# Peripherals.net
KiCad netlist of a schematic drawn in Altium Designer
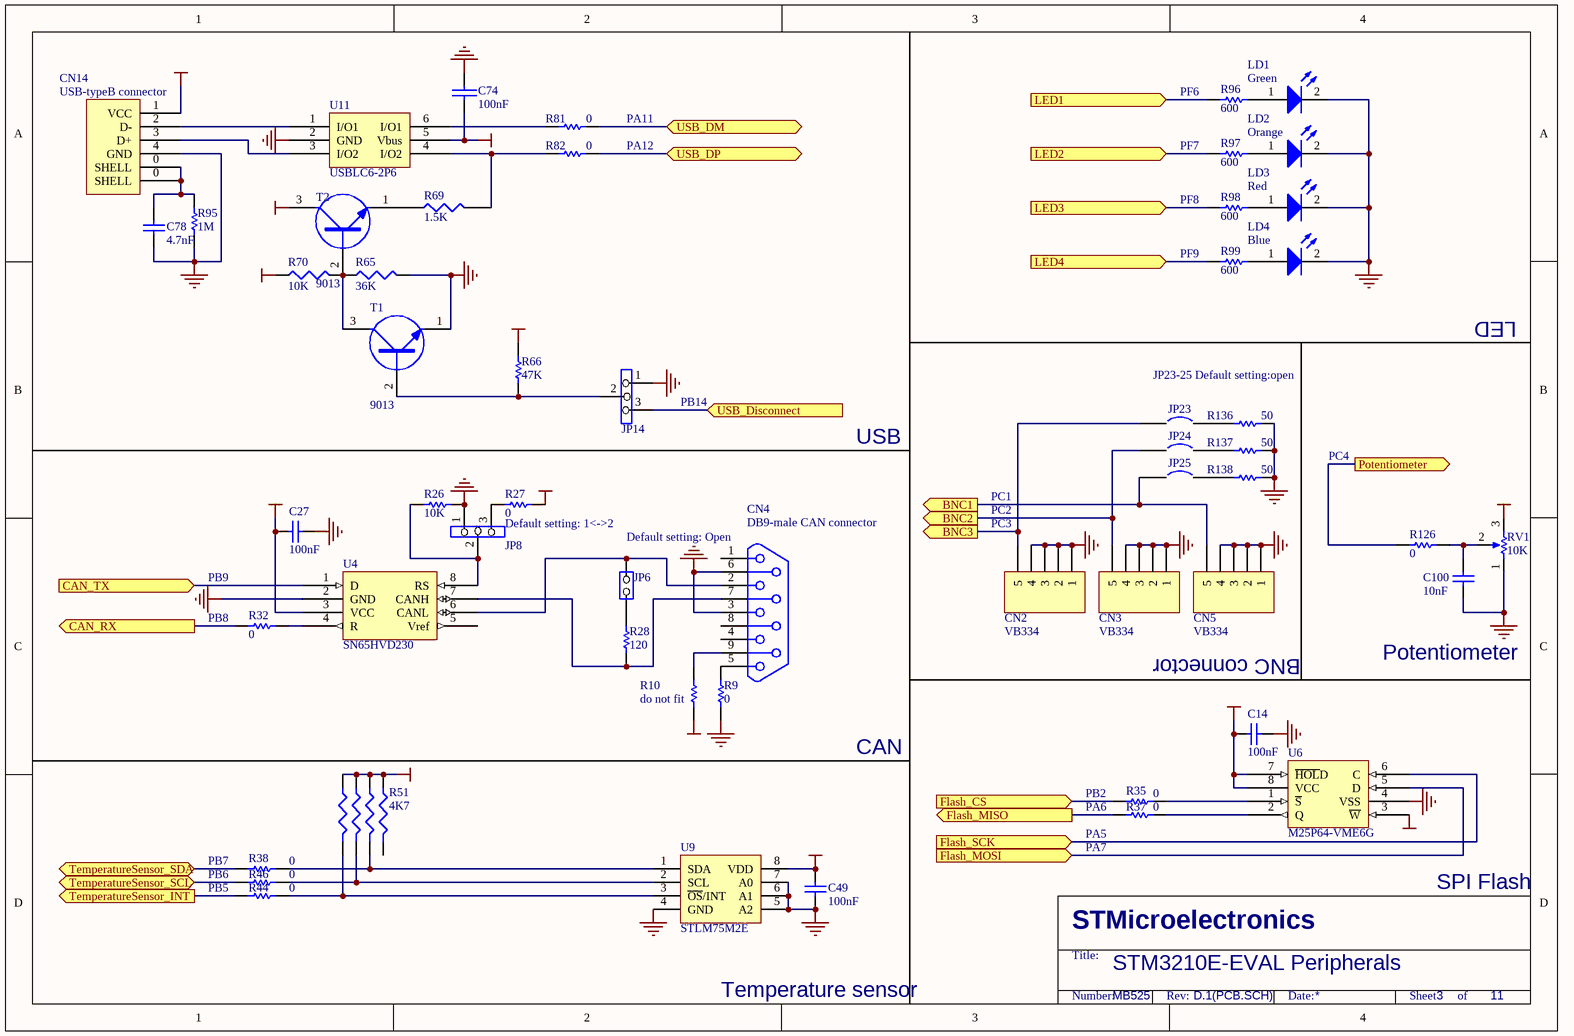
[diagram p0: Peripherals.SchDoc]

(export (version "E")
  (design (tool "Eeschema 10.0.6"))
  (components
    (comp (ref "C14")
      (value "100nF")
      (footprint "0603P")
      (description "Capacitor")
      (fields (field (name "PUBLISHER") "Altium Limited"))
      (libsource (lib "Miscellaneous Devices") (part "CAP"))
    )
    (comp (ref "C27")
      (value "100nF")
      (footprint "0603P")
      (description "Capacitor")
      (fields (field (name "PUBLISHER") "Altium Limited"))
      (libsource (lib "Miscellaneous Devices") (part "CAP"))
    )
    (comp (ref "C49")
      (value "100nF")
      (footprint "0603P")
      (description "Capacitor")
      (fields (field (name "PUBLISHER") "Altium Limited"))
      (libsource (lib "Miscellaneous Devices") (part "cap"))
    )
    (comp (ref "C74")
      (value "100nF")
      (footprint "0603P")
      (description "Capacitor")
      (libsource (lib "*") (part "CAP"))
    )
    (comp (ref "C78")
      (value "4.7nF")
      (description "Capacitor")
      (fields (field (name "PUBLISHER") "Altium Limited"))
      (libsource (lib "Miscellaneous Devices") (part "CAP"))
    )
    (comp (ref "C100")
      (value "10nF")
      (description "Capacitor")
      (fields (field (name "PUBLISHER") "Altium Limited"))
      (libsource (lib "Miscellaneous Devices") (part "CAP"))
    )
    (comp (ref "CN2")
      (value "VB334")
      (footprint "VB334")
      (description "Header, 5-Pin")
      (fields (field (name "PUBLISHER") "Altium Limited"))
      (libsource (lib "Miscellaneous Connectors") (part "Header 5"))
    )
    (comp (ref "CN3")
      (value "VB334")
      (footprint "VB334")
      (description "Header, 5-Pin")
      (fields (field (name "PUBLISHER") "Altium Limited"))
      (libsource (lib "Miscellaneous Connectors") (part "Header 5"))
    )
    (comp (ref "CN4") (value "DB9-male CAN connector") (footprint "DB9/M") (libsource (lib "*") (part "DB9")))
    (comp (ref "CN5")
      (value "VB334")
      (footprint "VB334")
      (description "Header, 5-Pin")
      (fields (field (name "PUBLISHER") "Altium Limited"))
      (libsource (lib "Miscellaneous Connectors") (part "Header 5"))
    )
    (comp (ref "CN14")
      (value "USB-typeB connector")
      (footprint "USB-B")
      (description "USB-B")
      (libsource (lib "Documents") (part "USB-B"))
    )
    (comp (ref "JP6") (value "~") (footprint "SIP2") (libsource (lib "*") (part "JP2")))
    (comp (ref "JP8") (value "~") (footprint "SIP3") (libsource (lib "STR910_SCHLIB") (part "Jumper3")))
    (comp (ref "JP14") (value "~") (footprint "SIP3") (libsource (lib "STR910_SCHLIB") (part "Jumper3")))
    (comp (ref "JP23")
      (value "~")
      (footprint "SPST-2")
      (description "Circuit Breaker")
      (fields (field (name "PUBLISHER") "Altium Limited"))
      (libsource (lib "Miscellaneous Devices") (part "Circuit Breaker"))
    )
    (comp (ref "JP24")
      (value "~")
      (footprint "SPST-2")
      (description "Circuit Breaker")
      (fields (field (name "PUBLISHER") "Altium Limited"))
      (libsource (lib "Miscellaneous Devices") (part "Circuit Breaker"))
    )
    (comp (ref "JP25")
      (value "~")
      (footprint "SPST-2")
      (description "Circuit Breaker")
      (fields (field (name "PUBLISHER") "Altium Limited"))
      (libsource (lib "Miscellaneous Devices") (part "Circuit Breaker"))
    )
    (comp (ref "LD1")
      (value "Green")
      (footprint "D0603")
      (description "Typical RED, GREEN, YELLOW, AMBER GaAs LED")
      (fields (field (name "PUBLISHER") "Altium Limited"))
      (libsource (lib "Miscellaneous Devices") (part "LED2"))
    )
    (comp (ref "LD2")
      (value "Orange")
      (footprint "D0603")
      (description "Typical RED, GREEN, YELLOW, AMBER GaAs LED")
      (fields (field (name "PUBLISHER") "Altium Limited"))
      (libsource (lib "Miscellaneous Devices") (part "LED2"))
    )
    (comp (ref "LD3")
      (value "Red")
      (footprint "D0603")
      (description "Typical RED, GREEN, YELLOW, AMBER GaAs LED")
      (fields (field (name "PUBLISHER") "Altium Limited"))
      (libsource (lib "Miscellaneous Devices") (part "LED2"))
    )
    (comp (ref "LD4")
      (value "Blue")
      (footprint "D0603")
      (description "Typical RED, GREEN, YELLOW, AMBER GaAs LED")
      (fields (field (name "PUBLISHER") "Altium Limited"))
      (libsource (lib "Miscellaneous Devices") (part "LED2"))
    )
    (comp (ref "R9")
      (value "0")
      (description "Resistor")
      (fields (field (name "PUBLISHER") "Altium Limited"))
      (libsource (lib "Miscellaneous Devices") (part "res1"))
    )
    (comp (ref "R10")
      (value "do not fit")
      (description "Resistor")
      (fields (field (name "PUBLISHER") "Altium Limited"))
      (libsource (lib "Miscellaneous Devices") (part "res1"))
    )
    (comp (ref "R26")
      (value "10K")
      (description "Resistor")
      (fields (field (name "PUBLISHER") "Altium Limited"))
      (libsource (lib "Miscellaneous Devices") (part "res1"))
    )
    (comp (ref "R27")
      (value "0")
      (description "Resistor")
      (fields (field (name "PUBLISHER") "Altium Limited"))
      (libsource (lib "Miscellaneous Devices") (part "res1"))
    )
    (comp (ref "R28")
      (value "120")
      (description "Resistor")
      (fields (field (name "PUBLISHER") "Altium Limited"))
      (libsource (lib "Miscellaneous Devices") (part "res1"))
    )
    (comp (ref "R32")
      (value "0")
      (description "Resistor")
      (fields (field (name "PUBLISHER") "Altium Limited"))
      (libsource (lib "Miscellaneous Devices") (part "Res1"))
    )
    (comp (ref "R35")
      (value "0")
      (description "Resistor")
      (fields (field (name "PUBLISHER") "Altium Limited"))
      (libsource (lib "Miscellaneous Devices") (part "Res1"))
    )
    (comp (ref "R37")
      (value "0")
      (description "Resistor")
      (fields (field (name "PUBLISHER") "Altium Limited"))
      (libsource (lib "Miscellaneous Devices") (part "Res1"))
    )
    (comp (ref "R38")
      (value "0")
      (description "Resistor")
      (fields (field (name "PUBLISHER") "Altium Limited"))
      (libsource (lib "Miscellaneous Devices") (part "Res1"))
    )
    (comp (ref "R44")
      (value "0")
      (description "Resistor")
      (fields (field (name "PUBLISHER") "Altium Limited"))
      (libsource (lib "Miscellaneous Devices") (part "Res1"))
    )
    (comp (ref "R46")
      (value "0")
      (description "Resistor")
      (fields (field (name "PUBLISHER") "Altium Limited"))
      (libsource (lib "Miscellaneous Devices") (part "Res1"))
    )
    (comp (ref "R51") (value "4K7") (footprint "RES4B") (libsource (lib "*") (part "RES4B")))
    (comp (ref "R65") (value "36K") (footprint "0603") (libsource (lib "*") (part "R")))
    (comp (ref "R66")
      (value "47K")
      (description "Resistor")
      (fields (field (name "PUBLISHER") "Altium Limited"))
      (libsource (lib "Miscellaneous Devices") (part "Res1"))
    )
    (comp (ref "R69") (value "1.5K") (footprint "0603") (libsource (lib "*") (part "RES1")))
    (comp (ref "R70") (value "10K") (footprint "0603") (libsource (lib "*") (part "R")))
    (comp (ref "R81")
      (value "0")
      (description "Resistor")
      (fields (field (name "PUBLISHER") "Altium Limited"))
      (libsource (lib "Miscellaneous Devices") (part "Res1"))
    )
    (comp (ref "R82")
      (value "0")
      (description "Resistor")
      (fields (field (name "PUBLISHER") "Altium Limited"))
      (libsource (lib "Miscellaneous Devices") (part "Res1"))
    )
    (comp (ref "R95")
      (value "1M")
      (description "Resistor")
      (fields (field (name "PUBLISHER") "Altium Limited"))
      (libsource (lib "Miscellaneous Devices") (part "Res1"))
    )
    (comp (ref "R96")
      (value "600")
      (description "Resistor")
      (fields (field (name "PUBLISHER") "Altium Limited"))
      (libsource (lib "Miscellaneous Devices") (part "Res1"))
    )
    (comp (ref "R97")
      (value "600")
      (description "Resistor")
      (fields (field (name "PUBLISHER") "Altium Limited"))
      (libsource (lib "Miscellaneous Devices") (part "Res1"))
    )
    (comp (ref "R98")
      (value "600")
      (description "Resistor")
      (fields (field (name "PUBLISHER") "Altium Limited"))
      (libsource (lib "Miscellaneous Devices") (part "Res1"))
    )
    (comp (ref "R99")
      (value "600")
      (description "Resistor")
      (fields (field (name "PUBLISHER") "Altium Limited"))
      (libsource (lib "Miscellaneous Devices") (part "Res1"))
    )
    (comp (ref "R126")
      (value "0")
      (description "Resistor")
      (fields (field (name "PUBLISHER") "Altium Limited"))
      (libsource (lib "Miscellaneous Devices") (part "Res1"))
    )
    (comp (ref "R136")
      (value "50")
      (description "Resistor")
      (fields (field (name "PUBLISHER") "Altium Limited"))
      (libsource (lib "Miscellaneous Devices") (part "Res1"))
    )
    (comp (ref "R137")
      (value "50")
      (description "Resistor")
      (fields (field (name "PUBLISHER") "Altium Limited"))
      (libsource (lib "Miscellaneous Devices") (part "Res1"))
    )
    (comp (ref "R138")
      (value "50")
      (description "Resistor")
      (fields (field (name "PUBLISHER") "Altium Limited"))
      (libsource (lib "Miscellaneous Devices") (part "Res1"))
    )
    (comp (ref "RV1") (value "10K") (footprint "ADJRH") (libsource (lib "STR910_SCHLIB") (part "RV")))
    (comp (ref "T1") (value "9013") (footprint "SOT-23") (libsource (lib "*") (part "NPN")))
    (comp (ref "T2") (value "9013") (footprint "SOT-23") (libsource (lib "*") (part "NPN")))
    (comp (ref "U4")
      (value "SN65HVD230")
      (footprint "SO8")
      (libsource (lib "STR910_SCHLIB") (part "SN65HVD230D"))
    )
    (comp (ref "U6")
      (value "M25P64-VME6G")
      (footprint "VDFPN8(8*6)")
      (libsource (lib "STR910_SCHLIB") (part "M25P64-VME6G"))
    )
    (comp (ref "U9") (value "STLM75M2E") (footprint "SO8") (libsource (lib "MB525") (part "STLM75DW2F")))
    (comp (ref "U11")
      (value "USBLC6-2P6")
      (footprint "SOT-666")
      (libsource (lib "STR910_SCHLIB") (part "USBLC6-2"))
    )
  )
  (nets
    (net (code "1") (name "+3V3") (class "Default")
      (node (ref "C14") (pin "2") (pinfunction "2_2") (pintype "passive"))
      (node (ref "C27") (pin "2") (pinfunction "2_2") (pintype "passive"))
      (node (ref "C49") (pin "2") (pinfunction "2_2") (pintype "passive"))
      (node (ref "R10") (pin "1") (pinfunction "1_1") (pintype "passive"))
      (node (ref "R27") (pin "2") (pinfunction "2_2") (pintype "passive"))
      (node (ref "R51") (pin "1") (pinfunction "R0_1") (pintype "passive"))
      (node (ref "R51") (pin "3") (pinfunction "R2_3") (pintype "passive"))
      (node (ref "R51") (pin "5") (pinfunction "R3_5") (pintype "passive"))
      (node (ref "R51") (pin "7") (pinfunction "R1_7") (pintype "passive"))
      (node (ref "R66") (pin "2") (pinfunction "2_2") (pintype "passive"))
      (node (ref "RV1") (pin "3") (pinfunction "TOP_3") (pintype "passive"))
      (node (ref "T2") (pin "3") (pinfunction "C_3") (pintype "passive"))
      (node (ref "U4") (pin "3") (pinfunction "VCC_3") (pintype "power_in"))
      (node (ref "U6") (pin "3") (pinfunction "~{W}_3") (pintype "input"))
      (node (ref "U6") (pin "7") (pinfunction "~{HOL}D_7") (pintype "input"))
      (node (ref "U6") (pin "8") (pinfunction "VCC_8") (pintype "power_in"))
      (node (ref "U9") (pin "8") (pinfunction "VDD_8") (pintype "passive"))
    )
    (net (code "2") (name "/BNC1") (class "Default")
      (node (ref "CN5") (pin "5") (pinfunction "5_5") (pintype "passive"))
      (node (ref "JP25") (pin "1") (pinfunction "1_1") (pintype "passive"))
    )
    (net (code "3") (name "/BNC2") (class "Default")
      (node (ref "CN3") (pin "5") (pinfunction "5_5") (pintype "passive"))
      (node (ref "JP24") (pin "1") (pinfunction "1_1") (pintype "passive"))
    )
    (net (code "4") (name "/BNC3") (class "Default")
      (node (ref "CN2") (pin "5") (pinfunction "5_5") (pintype "passive"))
      (node (ref "JP23") (pin "1") (pinfunction "1_1") (pintype "passive"))
    )
    (net (code "5") (name "/CAN_RX") (class "Default")
      (node (ref "R32") (pin "2") (pinfunction "2_2") (pintype "passive"))
    )
    (net (code "6") (name "/CAN_TX") (class "Default")
      (node (ref "U4") (pin "1") (pinfunction "D_1") (pintype "input"))
    )
    (net (code "7") (name "/Flash_CS") (class "Default")
      (node (ref "R35") (pin "2") (pinfunction "2_2") (pintype "passive"))
    )
    (net (code "8") (name "/Flash_MISO") (class "Default")
      (node (ref "R37") (pin "1") (pinfunction "1_1") (pintype "passive"))
    )
    (net (code "9") (name "/Flash_MOSI") (class "Default")
      (node (ref "U6") (pin "5") (pinfunction "D_5") (pintype "input"))
    )
    (net (code "10") (name "/Flash_SCK") (class "Default")
      (node (ref "U6") (pin "6") (pinfunction "C_6") (pintype "input"))
    )
    (net (code "11") (name "/LED1") (class "Default")
      (node (ref "R96") (pin "2") (pinfunction "2_2") (pintype "passive"))
    )
    (net (code "12") (name "/LED2") (class "Default")
      (node (ref "R97") (pin "2") (pinfunction "2_2") (pintype "passive"))
    )
    (net (code "13") (name "/LED3") (class "Default")
      (node (ref "R98") (pin "2") (pinfunction "2_2") (pintype "passive"))
    )
    (net (code "14") (name "/LED4") (class "Default")
      (node (ref "R99") (pin "2") (pinfunction "2_2") (pintype "passive"))
    )
    (net (code "15") (name "/Potentiometer") (class "Default")
      (node (ref "R126") (pin "1") (pinfunction "1_1") (pintype "passive"))
    )
    (net (code "16") (name "/TemperatureSensor_INT") (class "Default")
      (node (ref "R46") (pin "2") (pinfunction "2_2") (pintype "passive"))
    )
    (net (code "17") (name "/TemperatureSensor_SCL") (class "Default")
      (node (ref "R44") (pin "2") (pinfunction "2_2") (pintype "passive"))
    )
    (net (code "18") (name "/TemperatureSensor_SDA") (class "Default")
      (node (ref "R38") (pin "2") (pinfunction "2_2") (pintype "passive"))
    )
    (net (code "19") (name "/USB_DM") (class "Default")
      (node (ref "R81") (pin "1") (pinfunction "1_1") (pintype "passive"))
    )
    (net (code "20") (name "/USB_DP") (class "Default")
      (node (ref "R82") (pin "1") (pinfunction "1_1") (pintype "passive"))
    )
    (net (code "21") (name "/USB_Disconnect") (class "Default")
      (node (ref "JP14") (pin "3") (pintype "passive"))
    )
    (net (code "22") (name "GND") (class "Default")
      (node (ref "C100") (pin "1") (pinfunction "1_1") (pintype "passive"))
      (node (ref "C14") (pin "1") (pinfunction "1_1") (pintype "passive"))
      (node (ref "C27") (pin "1") (pinfunction "1_1") (pintype "passive"))
      (node (ref "C49") (pin "1") (pinfunction "1_1") (pintype "passive"))
      (node (ref "C74") (pin "1") (pinfunction "1_1") (pintype "passive"))
      (node (ref "C78") (pin "1") (pinfunction "1_1") (pintype "passive"))
      (node (ref "CN14") (pin "4") (pinfunction "GND_4") (pintype "passive"))
      (node (ref "CN2") (pin "1") (pinfunction "1_1") (pintype "passive"))
      (node (ref "CN2") (pin "2") (pinfunction "2_2") (pintype "passive"))
      (node (ref "CN2") (pin "3") (pinfunction "3_3") (pintype "passive"))
      (node (ref "CN2") (pin "4") (pinfunction "4_4") (pintype "passive"))
      (node (ref "CN3") (pin "1") (pinfunction "1_1") (pintype "passive"))
      (node (ref "CN3") (pin "2") (pinfunction "2_2") (pintype "passive"))
      (node (ref "CN3") (pin "3") (pinfunction "3_3") (pintype "passive"))
      (node (ref "CN3") (pin "4") (pinfunction "4_4") (pintype "passive"))
      (node (ref "CN4") (pin "3") (pinfunction "3_3") (pintype "passive"))
      (node (ref "CN4") (pin "6") (pinfunction "6_6") (pintype "passive"))
      (node (ref "CN5") (pin "1") (pinfunction "1_1") (pintype "passive"))
      (node (ref "CN5") (pin "2") (pinfunction "2_2") (pintype "passive"))
      (node (ref "CN5") (pin "3") (pinfunction "3_3") (pintype "passive"))
      (node (ref "CN5") (pin "4") (pinfunction "4_4") (pintype "passive"))
      (node (ref "JP14") (pin "1") (pintype "passive"))
      (node (ref "JP8") (pin "1") (pintype "passive"))
      (node (ref "LD1") (pin "2") (pinfunction "K_2") (pintype "passive"))
      (node (ref "LD2") (pin "2") (pinfunction "K_2") (pintype "passive"))
      (node (ref "LD3") (pin "2") (pinfunction "K_2") (pintype "passive"))
      (node (ref "LD4") (pin "2") (pinfunction "K_2") (pintype "passive"))
      (node (ref "R136") (pin "2") (pinfunction "2_2") (pintype "passive"))
      (node (ref "R137") (pin "2") (pinfunction "2_2") (pintype "passive"))
      (node (ref "R138") (pin "2") (pinfunction "2_2") (pintype "passive"))
      (node (ref "R26") (pin "2") (pinfunction "2_2") (pintype "passive"))
      (node (ref "R65") (pin "2") (pinfunction "2_2") (pintype "passive"))
      (node (ref "R9") (pin "1") (pinfunction "1_1") (pintype "passive"))
      (node (ref "R95") (pin "1") (pinfunction "1_1") (pintype "passive"))
      (node (ref "RV1") (pin "1") (pinfunction "BOT_1") (pintype "passive"))
      (node (ref "T1") (pin "1") (pinfunction "E_1") (pintype "passive"))
      (node (ref "U11") (pin "2") (pinfunction "GND_2") (pintype "passive"))
      (node (ref "U4") (pin "2") (pinfunction "GND_2") (pintype "power_in"))
      (node (ref "U6") (pin "4") (pinfunction "VSS_4") (pintype "power_in"))
      (node (ref "U9") (pin "4") (pinfunction "GND_4") (pintype "passive"))
      (node (ref "U9") (pin "5") (pinfunction "A2_5") (pintype "passive"))
      (node (ref "U9") (pin "6") (pinfunction "A1_6") (pintype "passive"))
      (node (ref "U9") (pin "7") (pinfunction "A0_7") (pintype "passive"))
    )
    (net (code "23") (name "Net-(CN4-Pad5)") (class "Default")
      (node (ref "CN4") (pin "5") (pinfunction "5_5") (pintype "passive"))
      (node (ref "R9") (pin "2") (pinfunction "2_2") (pintype "passive"))
    )
    (net (code "24") (name "Net-(CN4-Pad9)") (class "Default")
      (node (ref "CN4") (pin "9") (pinfunction "9_9") (pintype "passive"))
      (node (ref "R10") (pin "2") (pinfunction "2_2") (pintype "passive"))
    )
    (net (code "25") (name "Net-(CN14-D+)") (class "Default")
      (node (ref "CN14") (pin "3") (pinfunction "D+_3") (pintype "passive"))
      (node (ref "U11") (pin "3") (pinfunction "I/O2_3") (pintype "passive"))
    )
    (net (code "26") (name "Net-(CN14-D-)") (class "Default")
      (node (ref "CN14") (pin "2") (pinfunction "D-_2") (pintype "passive"))
      (node (ref "U11") (pin "1") (pinfunction "I/O1_1") (pintype "passive"))
    )
    (net (code "27") (name "Net-(CN14-SHELL)") (class "Default")
      (node (ref "C78") (pin "2") (pinfunction "2_2") (pintype "passive"))
      (node (ref "CN14") (pin "0") (pinfunction "SHELL_0") (pintype "passive"))
      (node (ref "R95") (pin "2") (pinfunction "2_2") (pintype "passive"))
    )
    (net (code "28") (name "Net-(JP6-COMMON)") (class "Default")
      (node (ref "JP6") (pin "1") (pinfunction "COMMON_1") (pintype "passive"))
      (node (ref "R28") (pin "2") (pinfunction "2_2") (pintype "passive"))
    )
    (net (code "29") (name "Net-(JP6-NO)") (class "Default")
      (node (ref "CN4") (pin "2") (pinfunction "2_2") (pintype "passive"))
      (node (ref "JP6") (pin "2") (pinfunction "NO_2") (pintype "passive"))
      (node (ref "U4") (pin "6") (pinfunction "CANL_6") (pintype "bidirectional"))
    )
    (net (code "30") (name "Net-(JP8-Pad3)") (class "Default")
      (node (ref "JP8") (pin "3") (pintype "passive"))
      (node (ref "R27") (pin "1") (pinfunction "1_1") (pintype "passive"))
    )
    (net (code "31") (name "Net-(JP23-Pad2)") (class "Default")
      (node (ref "JP23") (pin "2") (pinfunction "2_2") (pintype "passive"))
      (node (ref "R136") (pin "1") (pinfunction "1_1") (pintype "passive"))
    )
    (net (code "32") (name "Net-(JP24-Pad2)") (class "Default")
      (node (ref "JP24") (pin "2") (pinfunction "2_2") (pintype "passive"))
      (node (ref "R137") (pin "1") (pinfunction "1_1") (pintype "passive"))
    )
    (net (code "33") (name "Net-(JP25-Pad2)") (class "Default")
      (node (ref "JP25") (pin "2") (pinfunction "2_2") (pintype "passive"))
      (node (ref "R138") (pin "1") (pinfunction "1_1") (pintype "passive"))
    )
    (net (code "34") (name "Net-(LD1-A)") (class "Default")
      (node (ref "LD1") (pin "1") (pinfunction "A_1") (pintype "passive"))
      (node (ref "R96") (pin "1") (pinfunction "1_1") (pintype "passive"))
    )
    (net (code "35") (name "Net-(LD2-A)") (class "Default")
      (node (ref "LD2") (pin "1") (pinfunction "A_1") (pintype "passive"))
      (node (ref "R97") (pin "1") (pinfunction "1_1") (pintype "passive"))
    )
    (net (code "36") (name "Net-(LD3-A)") (class "Default")
      (node (ref "LD3") (pin "1") (pinfunction "A_1") (pintype "passive"))
      (node (ref "R98") (pin "1") (pinfunction "1_1") (pintype "passive"))
    )
    (net (code "37") (name "Net-(LD4-A)") (class "Default")
      (node (ref "LD4") (pin "1") (pinfunction "A_1") (pintype "passive"))
      (node (ref "R99") (pin "1") (pinfunction "1_1") (pintype "passive"))
    )
    (net (code "38") (name "Net-(R69-Pad2)") (class "Default")
      (node (ref "R69") (pin "2") (pinfunction "2_2") (pintype "passive"))
      (node (ref "R82") (pin "2") (pinfunction "2_2") (pintype "passive"))
      (node (ref "U11") (pin "4") (pinfunction "I/O2_4") (pintype "passive"))
    )
    (net (code "39") (name "Net-(R81-Pad2)") (class "Default")
      (node (ref "R81") (pin "2") (pinfunction "2_2") (pintype "passive"))
      (node (ref "U11") (pin "6") (pinfunction "I/O1_6") (pintype "passive"))
    )
    (net (code "40") (name "Net-(RV1-TAP)") (class "Default")
      (node (ref "C100") (pin "2") (pinfunction "2_2") (pintype "passive"))
      (node (ref "R126") (pin "2") (pinfunction "2_2") (pintype "passive"))
      (node (ref "RV1") (pin "2") (pinfunction "TAP_2") (pintype "passive"))
    )
    (net (code "41") (name "Net-(T1-B)") (class "Default")
      (node (ref "JP14") (pin "2") (pintype "passive"))
      (node (ref "R66") (pin "1") (pinfunction "1_1") (pintype "passive"))
      (node (ref "T1") (pin "2") (pinfunction "B_2") (pintype "passive"))
    )
    (net (code "42") (name "Net-(T1-C)") (class "Default")
      (node (ref "R65") (pin "1") (pinfunction "1_1") (pintype "passive"))
      (node (ref "R70") (pin "2") (pinfunction "2_2") (pintype "passive"))
      (node (ref "T1") (pin "3") (pinfunction "C_3") (pintype "passive"))
      (node (ref "T2") (pin "2") (pinfunction "B_2") (pintype "passive"))
    )
    (net (code "43") (name "Net-(T2-E)") (class "Default")
      (node (ref "R69") (pin "1") (pinfunction "1_1") (pintype "passive"))
      (node (ref "T2") (pin "1") (pinfunction "E_1") (pintype "passive"))
    )
    (net (code "44") (name "Net-(U4-CANH)") (class "Default")
      (node (ref "CN4") (pin "7") (pinfunction "7_7") (pintype "passive"))
      (node (ref "R28") (pin "1") (pinfunction "1_1") (pintype "passive"))
      (node (ref "U4") (pin "7") (pinfunction "CANH_7") (pintype "bidirectional"))
    )
    (net (code "45") (name "Net-(U4-R)") (class "Default")
      (node (ref "R32") (pin "1") (pinfunction "1_1") (pintype "passive"))
      (node (ref "U4") (pin "4") (pinfunction "R_4") (pintype "output"))
    )
    (net (code "46") (name "Net-(U4-RS)") (class "Default")
      (node (ref "JP8") (pin "2") (pintype "passive"))
      (node (ref "R26") (pin "1") (pinfunction "1_1") (pintype "passive"))
      (node (ref "U4") (pin "8") (pinfunction "RS_8") (pintype "input"))
    )
    (net (code "47") (name "Net-(U6-Q)") (class "Default")
      (node (ref "R37") (pin "2") (pinfunction "2_2") (pintype "passive"))
      (node (ref "U6") (pin "2") (pinfunction "Q_2") (pintype "output"))
    )
    (net (code "48") (name "Net-(U6-~{S})") (class "Default")
      (node (ref "R35") (pin "1") (pinfunction "1_1") (pintype "passive"))
      (node (ref "U6") (pin "1") (pinfunction "~{S}_1") (pintype "input"))
    )
    (net (code "49") (name "Net-(U9-SCL)") (class "Default")
      (node (ref "R44") (pin "1") (pinfunction "1_1") (pintype "passive"))
      (node (ref "R51") (pin "6") (pinfunction "R2_6") (pintype "passive"))
      (node (ref "U9") (pin "2") (pinfunction "SCL_2") (pintype "passive"))
    )
    (net (code "50") (name "Net-(U9-SDA)") (class "Default")
      (node (ref "R38") (pin "1") (pinfunction "1_1") (pintype "passive"))
      (node (ref "R51") (pin "4") (pinfunction "R3_4") (pintype "passive"))
      (node (ref "U9") (pin "1") (pinfunction "SDA_1") (pintype "passive"))
    )
    (net (code "51") (name "Net-(U9-~{OS}{slash}INT)") (class "Default")
      (node (ref "R46") (pin "1") (pinfunction "1_1") (pintype "passive"))
      (node (ref "R51") (pin "8") (pinfunction "R0_8") (pintype "passive"))
      (node (ref "U9") (pin "3") (pinfunction "~{OS}/INT_3") (pintype "passive"))
    )
    (net (code "52") (name "U5V") (class "Default")
      (node (ref "C74") (pin "2") (pinfunction "2_2") (pintype "passive"))
      (node (ref "CN14") (pin "1") (pinfunction "VCC_1") (pintype "passive"))
      (node (ref "R70") (pin "1") (pinfunction "1_1") (pintype "passive"))
      (node (ref "U11") (pin "5") (pinfunction "Vbus_5") (pintype "passive"))
    )
    (net (code "53") (name "unconnected-(CN4-Pad1)") (class "Default")
      (node (ref "CN4") (pin "1") (pinfunction "1_1") (pintype "passive"))
    )
    (net (code "54") (name "unconnected-(CN4-Pad4)") (class "Default")
      (node (ref "CN4") (pin "4") (pinfunction "4_4") (pintype "passive"))
    )
    (net (code "55") (name "unconnected-(CN4-Pad8)") (class "Default")
      (node (ref "CN4") (pin "8") (pinfunction "8_8") (pintype "passive"))
    )
    (net (code "56") (name "unconnected-(R51-R1-Pad2)") (class "Default")
      (node (ref "R51") (pin "2") (pinfunction "R1_2") (pintype "passive"))
    )
    (net (code "57") (name "unconnected-(U4-Vref-Pad5)") (class "Default")
      (node (ref "U4") (pin "5") (pinfunction "Vref_5") (pintype "output"))
    )
  )
)
